# 1-Schematic_BCD_to_Seven_Seg.net
KiCad netlist of a schematic drawn in EasyEDA
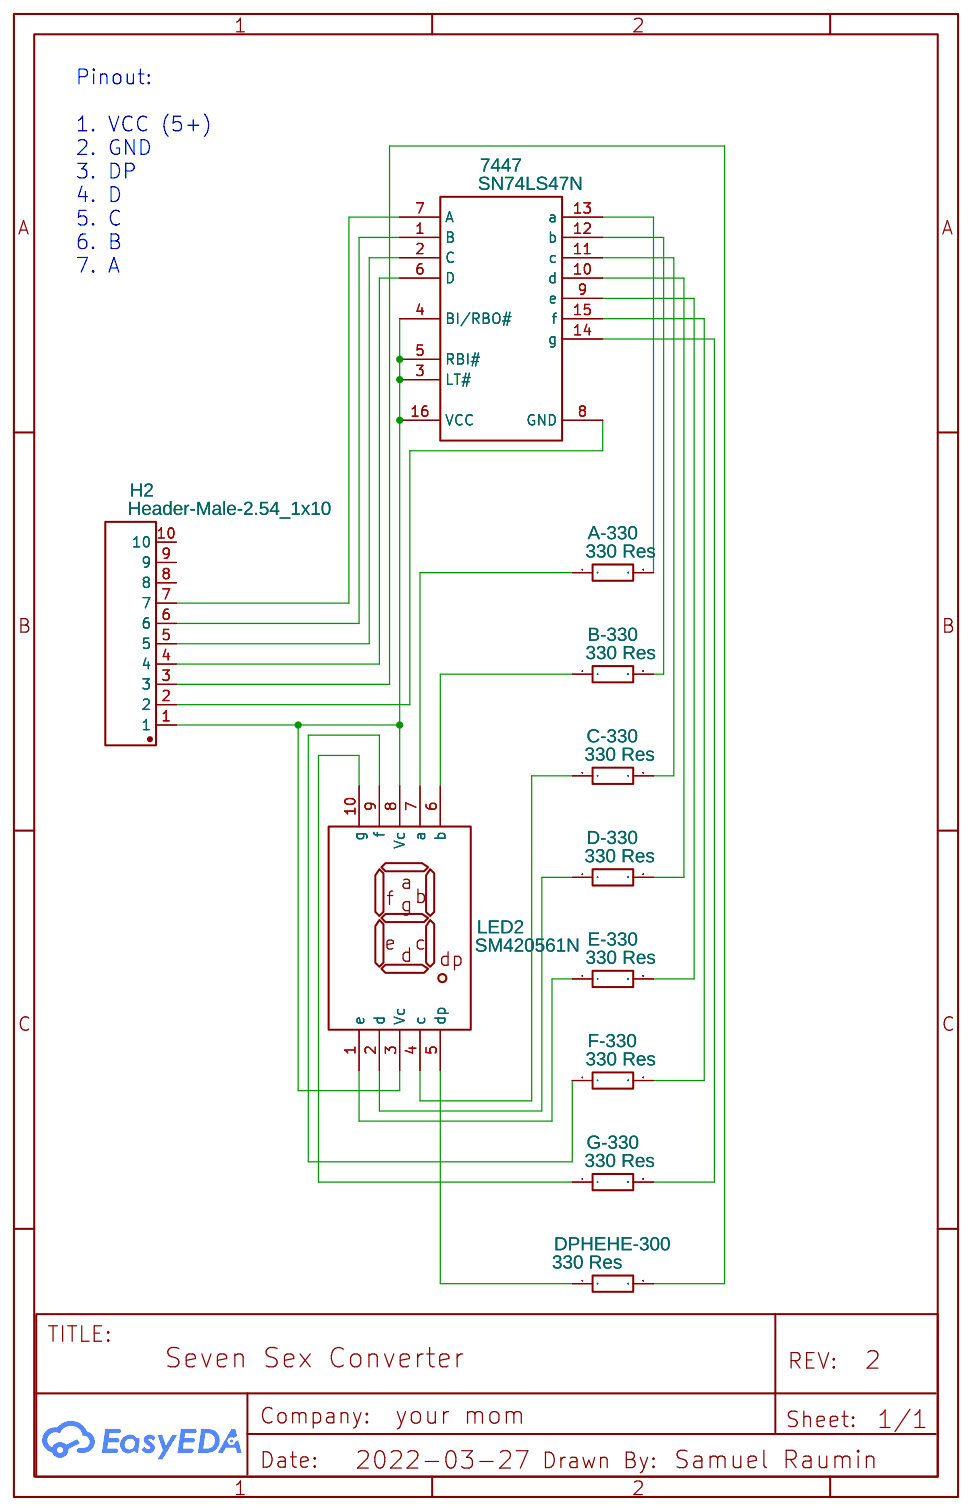
[diagram p0: schematic sheet]

(export (version "E")
  (design (tool "Eeschema 10.0.6"))
  (components
    (comp (ref "7447")
      (value "SN74LS47N")
      (fields (field (name "BOM_Supplier Part") "C129379"))
      (libsource (lib "") (part "SN74LS47N"))
    )
    (comp (ref "A-330")
      (value "330 Res")
      (fields
        (field (name "BOM_Manufacturer Part") "FR1/4W-10Ω±5%")
        (field (name "BOM_Supplier Part") "C138368")
      )
      (libsource (lib "") (part "FR1/4W-10Ω±5%_2"))
    )
    (comp (ref "B-330")
      (value "330 Res")
      (fields
        (field (name "BOM_Manufacturer Part") "FR1/4W-10Ω±5%")
        (field (name "BOM_Supplier Part") "C138368")
      )
      (libsource (lib "") (part "FR1/4W-10Ω±5%_1"))
    )
    (comp (ref "C-330")
      (value "330 Res")
      (fields
        (field (name "BOM_Manufacturer Part") "FR1/4W-10Ω±5%")
        (field (name "BOM_Supplier Part") "C138368")
      )
      (libsource (lib "") (part "FR1/4W-10Ω±5%_6"))
    )
    (comp (ref "D-330")
      (value "330 Res")
      (fields
        (field (name "BOM_Manufacturer Part") "FR1/4W-10Ω±5%")
        (field (name "BOM_Supplier Part") "C138368")
      )
      (libsource (lib "") (part "FR1/4W-10Ω±5%_3"))
    )
    (comp (ref "DPHEHE-300")
      (value "330 Res")
      (fields
        (field (name "BOM_Manufacturer Part") "FR1/4W-10Ω±5%")
        (field (name "BOM_Supplier Part") "C138368")
      )
      (libsource (lib "") (part "FR1/4W-10Ω±5%_4"))
    )
    (comp (ref "E-330")
      (value "330 Res")
      (fields
        (field (name "BOM_Manufacturer Part") "FR1/4W-10Ω±5%")
        (field (name "BOM_Supplier Part") "C138368")
      )
      (libsource (lib "") (part "FR1/4W-10Ω±5%_7"))
    )
    (comp (ref "F-330")
      (value "330 Res")
      (fields
        (field (name "BOM_Manufacturer Part") "FR1/4W-10Ω±5%")
        (field (name "BOM_Supplier Part") "C138368")
      )
      (libsource (lib "") (part "FR1/4W-10Ω±5%_5"))
    )
    (comp (ref "G-330")
      (value "330 Res")
      (fields
        (field (name "BOM_Manufacturer Part") "FR1/4W-10Ω±5%")
        (field (name "BOM_Supplier Part") "C138368")
      )
      (libsource (lib "") (part "FR1/4W-10Ω±5%"))
    )
    (comp (ref "H2")
      (value "Header-Male-2.54_1x10")
      (fields
        (field (name "BOM_Manufacturer Part") "Headers  Pins2.54mm1*10P")
        (field (name "BOM_Supplier Part") "C57369")
      )
      (libsource (lib "") (part "Header-Male-2.54_1x10"))
    )
    (comp (ref "LED2")
      (value "SM420561N")
      (fields (field (name "BOM_Supplier Part") "C141367"))
      (libsource (lib "") (part "SM420561N"))
    )
  )
  (nets
    (net (code "1") (name "Net-(7447-A)") (class "Default")
      (node (ref "7447") (pin "7") (pinfunction "A_7") (pintype "unspecified"))
      (node (ref "H2") (pin "7") (pinfunction "7_7") (pintype "unspecified"))
    )
    (net (code "2") (name "Net-(7447-B)") (class "Default")
      (node (ref "7447") (pin "1") (pinfunction "B_1") (pintype "unspecified"))
      (node (ref "H2") (pin "6") (pinfunction "6_6") (pintype "unspecified"))
    )
    (net (code "3") (name "Net-(7447-BI{slash}RBO#)") (class "Default")
      (node (ref "7447") (pin "16") (pinfunction "VCC_16") (pintype "passive"))
      (node (ref "7447") (pin "3") (pinfunction "LT#_3") (pintype "unspecified"))
      (node (ref "7447") (pin "4") (pinfunction "BI/RBO#_4") (pintype "bidirectional"))
      (node (ref "7447") (pin "5") (pinfunction "RBI#_5") (pintype "unspecified"))
      (node (ref "H2") (pin "1") (pinfunction "1_1") (pintype "unspecified"))
      (node (ref "LED2") (pin "3") (pinfunction "Vc_3") (pintype "input"))
      (node (ref "LED2") (pin "8") (pinfunction "Vc_8") (pintype "input"))
    )
    (net (code "4") (name "Net-(7447-C)") (class "Default")
      (node (ref "7447") (pin "2") (pinfunction "C_2") (pintype "unspecified"))
      (node (ref "H2") (pin "5") (pinfunction "5_5") (pintype "unspecified"))
    )
    (net (code "5") (name "Net-(7447-D)") (class "Default")
      (node (ref "7447") (pin "6") (pinfunction "D_6") (pintype "unspecified"))
      (node (ref "H2") (pin "4") (pinfunction "4_4") (pintype "unspecified"))
    )
    (net (code "6") (name "Net-(7447-GND)") (class "Default")
      (node (ref "7447") (pin "8") (pinfunction "GND_8") (pintype "passive"))
      (node (ref "H2") (pin "2") (pinfunction "2_2") (pintype "unspecified"))
    )
    (net (code "7") (name "Net-(7447-a)") (class "Default")
      (node (ref "7447") (pin "13") (pinfunction "a_13") (pintype "unspecified"))
      (node (ref "A-330") (pin "2") (pinfunction "2_2") (pintype "unspecified"))
    )
    (net (code "8") (name "Net-(7447-b)") (class "Default")
      (node (ref "7447") (pin "12") (pinfunction "b_12") (pintype "unspecified"))
      (node (ref "B-330") (pin "2") (pinfunction "2_2") (pintype "unspecified"))
    )
    (net (code "9") (name "Net-(7447-c)") (class "Default")
      (node (ref "7447") (pin "11") (pinfunction "c_11") (pintype "unspecified"))
      (node (ref "C-330") (pin "2") (pinfunction "2_2") (pintype "unspecified"))
    )
    (net (code "10") (name "Net-(7447-d)") (class "Default")
      (node (ref "7447") (pin "10") (pinfunction "d_10") (pintype "unspecified"))
      (node (ref "D-330") (pin "2") (pinfunction "2_2") (pintype "unspecified"))
    )
    (net (code "11") (name "Net-(7447-e)") (class "Default")
      (node (ref "7447") (pin "9") (pinfunction "e_9") (pintype "unspecified"))
      (node (ref "E-330") (pin "2") (pinfunction "2_2") (pintype "unspecified"))
    )
    (net (code "12") (name "Net-(7447-f)") (class "Default")
      (node (ref "7447") (pin "15") (pinfunction "f_15") (pintype "unspecified"))
      (node (ref "F-330") (pin "2") (pinfunction "2_2") (pintype "unspecified"))
    )
    (net (code "13") (name "Net-(7447-g)") (class "Default")
      (node (ref "7447") (pin "14") (pinfunction "g_14") (pintype "unspecified"))
      (node (ref "G-330") (pin "2") (pinfunction "2_2") (pintype "unspecified"))
    )
    (net (code "14") (name "Net-(DPHEHE-300-Pad2)") (class "Default")
      (node (ref "DPHEHE-300") (pin "2") (pinfunction "2_2") (pintype "unspecified"))
      (node (ref "H2") (pin "3") (pinfunction "3_3") (pintype "unspecified"))
    )
    (net (code "15") (name "Net-(LED2-a)") (class "Default")
      (node (ref "A-330") (pin "1") (pinfunction "1_1") (pintype "unspecified"))
      (node (ref "LED2") (pin "7") (pinfunction "a_7") (pintype "input"))
    )
    (net (code "16") (name "Net-(LED2-b)") (class "Default")
      (node (ref "B-330") (pin "1") (pinfunction "1_1") (pintype "unspecified"))
      (node (ref "LED2") (pin "6") (pinfunction "b_6") (pintype "input"))
    )
    (net (code "17") (name "Net-(LED2-c)") (class "Default")
      (node (ref "C-330") (pin "1") (pinfunction "1_1") (pintype "unspecified"))
      (node (ref "LED2") (pin "4") (pinfunction "c_4") (pintype "input"))
    )
    (net (code "18") (name "Net-(LED2-d)") (class "Default")
      (node (ref "D-330") (pin "1") (pinfunction "1_1") (pintype "unspecified"))
      (node (ref "LED2") (pin "2") (pinfunction "d_2") (pintype "input"))
    )
    (net (code "19") (name "Net-(LED2-dp)") (class "Default")
      (node (ref "DPHEHE-300") (pin "1") (pinfunction "1_1") (pintype "unspecified"))
      (node (ref "LED2") (pin "5") (pinfunction "dp_5") (pintype "input"))
    )
    (net (code "20") (name "Net-(LED2-e)") (class "Default")
      (node (ref "E-330") (pin "1") (pinfunction "1_1") (pintype "unspecified"))
      (node (ref "LED2") (pin "1") (pinfunction "e_1") (pintype "input"))
    )
    (net (code "21") (name "Net-(LED2-f)") (class "Default")
      (node (ref "F-330") (pin "1") (pinfunction "1_1") (pintype "unspecified"))
      (node (ref "LED2") (pin "9") (pinfunction "f_9") (pintype "input"))
    )
    (net (code "22") (name "Net-(LED2-g)") (class "Default")
      (node (ref "G-330") (pin "1") (pinfunction "1_1") (pintype "unspecified"))
      (node (ref "LED2") (pin "10") (pinfunction "g_10") (pintype "input"))
    )
    (net (code "23") (name "unconnected-(H2-Pad8)") (class "Default")
      (node (ref "H2") (pin "8") (pinfunction "8_8") (pintype "unspecified"))
    )
    (net (code "24") (name "unconnected-(H2-Pad9)") (class "Default")
      (node (ref "H2") (pin "9") (pinfunction "9_9") (pintype "unspecified"))
    )
    (net (code "25") (name "unconnected-(H2-Pad10)") (class "Default")
      (node (ref "H2") (pin "10") (pinfunction "10_10") (pintype "unspecified"))
    )
  )
)
